# 17-FPGA-02b.net
KiCad netlist of a schematic drawn in Altium Designer
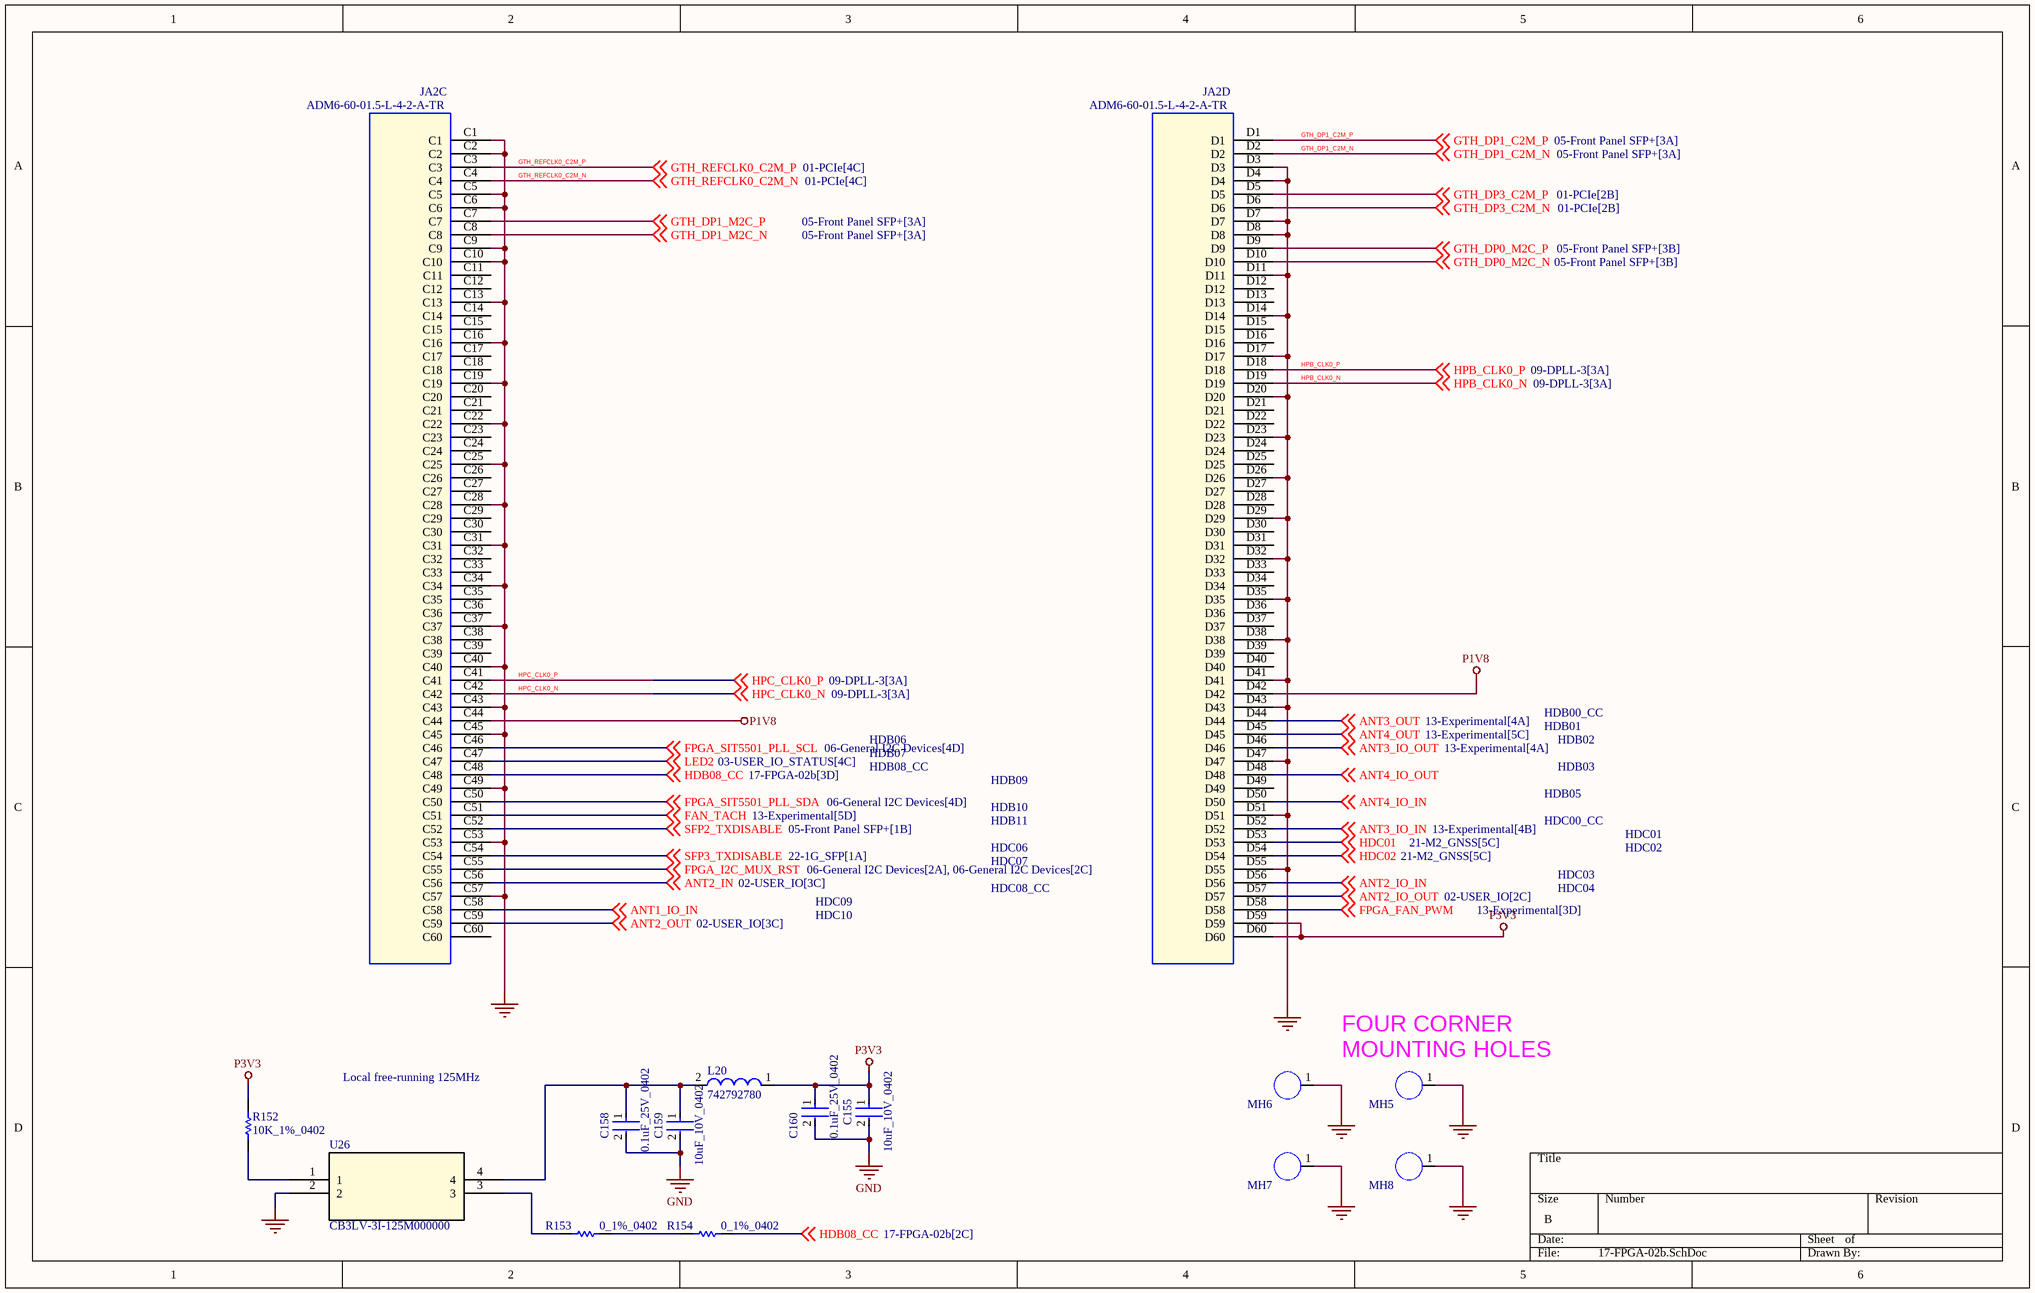
[diagram p0: 17-FPGA-02b.SchDoc]

(export (version "E")
  (design (tool "Eeschema 10.0.6"))
  (components
    (comp (ref "C155")
      (value "10uF_10V_0402")
      (footprint "FP-CL05A106MP5NUNC-MFG")
      (description "CAP CER 10UF 10V X5R 0402")
      (fields
        (field (name "OCTOPART") "https://octopart.com/cl05a106mp5nunc-samsung-22457395")
        (field (name "TOLERANCE") "20%")
      )
      (libsource (lib "Altium Content Vault") (part "b4654b650e69147ec39a6b967a45e02"))
    )
    (comp (ref "C158")
      (value "0.1uF_25V_0402")
      (footprint "FP-0402-L_1_0_1-W_0_5_0_1-IPC_C")
      (description "General Purpose Ceramic Capacitor, 0402, 100nF, 10%, X7R, 15%, 25V")
      (fields (field (name "VOLTAGE") "25V") (field (name "TOLERANCE") "10%"))
      (libsource (lib "Altium Content Vault") (part "b4654b650e69147ec39a6b967a45e02"))
    )
    (comp (ref "C159")
      (value "10uF_10V_0402")
      (footprint "FP-CL05A106MP5NUNC-MFG")
      (description "CAP CER 10UF 10V X5R 0402")
      (fields
        (field (name "OCTOPART") "https://octopart.com/cl05a106mp5nunc-samsung-22457395")
        (field (name "TOLERANCE") "20%")
      )
      (libsource (lib "Altium Content Vault") (part "b4654b650e69147ec39a6b967a45e02"))
    )
    (comp (ref "C160")
      (value "0.1uF_25V_0402")
      (footprint "FP-0402-L_1_0_1-W_0_5_0_1-IPC_C")
      (description "General Purpose Ceramic Capacitor, 0402, 100nF, 10%, X7R, 15%, 25V")
      (fields (field (name "VOLTAGE") "25V") (field (name "TOLERANCE") "10%"))
      (libsource (lib "Altium Content Vault") (part "b4654b650e69147ec39a6b967a45e02"))
    )
    (comp (ref "JA2")
      (value "ADM6-60-01.5-L-4-2-A-TR")
      (footprint "CON_SAMTEC_ADM6_60_4")
      (description "Conn Rcpt Male Vert 240 Pos 4x60 0.635mm P Black SMT")
      (fields (field (name "MANUFACTURER") "Samtec Inc.") (field (name "AGILE PART NUMBER") "CON-00383-01"))
      (libsource (lib "*") (part "SAMTEC-ADx6-60X4"))
    )
    (comp (ref "L20")
      (value "742792780")
      (footprint "SMD-0402")
      (description "SMD EMI Suppression Ferrite Bead WE-CBF, Z = 220 Ohm")
      (libsource (lib "Altium Content Vault") (part "PAS-IND-INDUCTOR-2"))
    )
    (comp (ref "MH5")
      (value "MH_NP_M3_SO_600")
      (footprint "MH_NP_M3_SO_600")
      (description "MOUNTING HOLE, NON-PLATED 3.4MM HOLE")
      (libsource (lib "*") (part "HOLE"))
    )
    (comp (ref "MH6")
      (value "MH_NP_M3_SO_600")
      (footprint "MH_NP_M3_SO_600")
      (description "MOUNTING HOLE, NON-PLATED 3.4MM HOLE")
      (libsource (lib "*") (part "HOLE"))
    )
    (comp (ref "MH7")
      (value "MH_NP_M3_SO_600")
      (footprint "MH_NP_M3_SO_600")
      (description "MOUNTING HOLE, NON-PLATED 3.4MM HOLE")
      (libsource (lib "*") (part "HOLE"))
    )
    (comp (ref "MH8")
      (value "MH_NP_M3_SO_600")
      (footprint "MH_NP_M3_SO_600")
      (description "MOUNTING HOLE, NON-PLATED 3.4MM HOLE")
      (libsource (lib "*") (part "HOLE"))
    )
    (comp (ref "R152")
      (value "10K_1%_0402")
      (footprint "RESC1005X40X25LL05T05")
      (description "Chip Resistor, 10 KOhm, +/- 1%, 0.1 W, -55 to 155 degC, 0402 (1005 Metric), RoHS, Tape and Reel")
      (fields (field (name "TOLERANCE") "1%") (field (name "MANUFACTURER") "Panasonic"))
      (libsource (lib "Altium Content Vault") (part "RES-2"))
    )
    (comp (ref "R153")
      (value "0_1%_0402")
      (footprint "RESC1005X40X25LL05T05")
      (description "Chip Resistor, 0 Ohm, 0.1 W, -55 to 155 degC, 0402 (1005 Metric), RoHS, Tape and Reel")
      (fields (field (name "MANUFACTURER") "Panasonic") (field (name "TOLERANCE") "5%"))
      (libsource (lib "Altium Content Vault") (part "RES-2"))
    )
    (comp (ref "R154")
      (value "0_1%_0402")
      (footprint "RESC1005X40X25LL05T05")
      (description "Chip Resistor, 0 Ohm, 0.1 W, -55 to 155 degC, 0402 (1005 Metric), RoHS, Tape and Reel")
      (fields (field (name "MANUFACTURER") "Panasonic") (field (name "TOLERANCE") "5%"))
      (libsource (lib "Altium Content Vault") (part "RES-2"))
    )
    (comp (ref "U26")
      (value "CB3LV-3I-125M000000")
      (footprint "CRYS_CB3LV-3I-14M7456_CTS")
      (description "No Description Available")
      (libsource (lib "CB3LV-3I-14M7456") (part "CB3LV-3I-14M7456"))
    )
  )
  (nets
    (net (code "1") (name "ANT1_IO_IN") (class "Default")
      (node (ref "JA2") (pin "C58") (pinfunction "C58_C58") (pintype "passive"))
    )
    (net (code "2") (name "ANT2_IN") (class "Default")
      (node (ref "JA2") (pin "C56") (pinfunction "C56_C56") (pintype "passive"))
    )
    (net (code "3") (name "ANT2_IO_IN") (class "Default")
      (node (ref "JA2") (pin "D56") (pinfunction "D56_D56") (pintype "passive"))
    )
    (net (code "4") (name "ANT2_IO_OUT") (class "Default")
      (node (ref "JA2") (pin "D57") (pinfunction "D57_D57") (pintype "passive"))
    )
    (net (code "5") (name "ANT2_OUT") (class "Default")
      (node (ref "JA2") (pin "C59") (pinfunction "C59_C59") (pintype "passive"))
    )
    (net (code "6") (name "ANT3_IO_IN") (class "Default")
      (node (ref "JA2") (pin "D52") (pinfunction "D52_D52") (pintype "passive"))
    )
    (net (code "7") (name "ANT3_IO_OUT") (class "Default")
      (node (ref "JA2") (pin "D46") (pinfunction "D46_D46") (pintype "passive"))
    )
    (net (code "8") (name "ANT3_OUT") (class "Default")
      (node (ref "JA2") (pin "D44") (pinfunction "D44_D44") (pintype "passive"))
    )
    (net (code "9") (name "ANT4_IO_IN") (class "Default")
      (node (ref "JA2") (pin "D50") (pinfunction "D50_D50") (pintype "passive"))
    )
    (net (code "10") (name "ANT4_IO_OUT") (class "Default")
      (node (ref "JA2") (pin "D48") (pinfunction "D48_D48") (pintype "passive"))
    )
    (net (code "11") (name "ANT4_OUT") (class "Default")
      (node (ref "JA2") (pin "D45") (pinfunction "D45_D45") (pintype "passive"))
    )
    (net (code "12") (name "FAN_TACH") (class "Default")
      (node (ref "JA2") (pin "C51") (pinfunction "C51_C51") (pintype "passive"))
    )
    (net (code "13") (name "FPGA_FAN_PWM") (class "Default")
      (node (ref "JA2") (pin "D58") (pinfunction "D58_D58") (pintype "passive"))
    )
    (net (code "14") (name "FPGA_I2C_MUX_RST") (class "Default")
      (node (ref "JA2") (pin "C55") (pinfunction "C55_C55") (pintype "passive"))
    )
    (net (code "15") (name "FPGA_SIT5501_PLL_SCL") (class "Default")
      (node (ref "JA2") (pin "C46") (pinfunction "C46_C46") (pintype "passive"))
    )
    (net (code "16") (name "FPGA_SIT5501_PLL_SDA") (class "Default")
      (node (ref "JA2") (pin "C50") (pinfunction "C50_C50") (pintype "passive"))
    )
    (net (code "17") (name "GND") (class "Default")
      (node (ref "C155") (pin "2") (pinfunction "2_2") (pintype "passive"))
      (node (ref "C158") (pin "2") (pinfunction "2_2") (pintype "passive"))
      (node (ref "C159") (pin "2") (pinfunction "2_2") (pintype "passive"))
      (node (ref "C160") (pin "2") (pinfunction "2_2") (pintype "passive"))
      (node (ref "JA2") (pin "C1") (pinfunction "C1_C1") (pintype "passive"))
      (node (ref "JA2") (pin "C10") (pinfunction "C10_C10") (pintype "passive"))
      (node (ref "JA2") (pin "C13") (pinfunction "C13_C13") (pintype "passive"))
      (node (ref "JA2") (pin "C16") (pinfunction "C16_C16") (pintype "passive"))
      (node (ref "JA2") (pin "C19") (pinfunction "C19_C19") (pintype "passive"))
      (node (ref "JA2") (pin "C2") (pinfunction "C2_C2") (pintype "passive"))
      (node (ref "JA2") (pin "C22") (pinfunction "C22_C22") (pintype "passive"))
      (node (ref "JA2") (pin "C25") (pinfunction "C25_C25") (pintype "passive"))
      (node (ref "JA2") (pin "C28") (pinfunction "C28_C28") (pintype "passive"))
      (node (ref "JA2") (pin "C31") (pinfunction "C31_C31") (pintype "passive"))
      (node (ref "JA2") (pin "C34") (pinfunction "C34_C34") (pintype "passive"))
      (node (ref "JA2") (pin "C37") (pinfunction "C37_C37") (pintype "passive"))
      (node (ref "JA2") (pin "C40") (pinfunction "C40_C40") (pintype "passive"))
      (node (ref "JA2") (pin "C43") (pinfunction "C43_C43") (pintype "passive"))
      (node (ref "JA2") (pin "C45") (pinfunction "C45_C45") (pintype "passive"))
      (node (ref "JA2") (pin "C49") (pinfunction "C49_C49") (pintype "passive"))
      (node (ref "JA2") (pin "C5") (pinfunction "C5_C5") (pintype "passive"))
      (node (ref "JA2") (pin "C53") (pinfunction "C53_C53") (pintype "passive"))
      (node (ref "JA2") (pin "C57") (pinfunction "C57_C57") (pintype "passive"))
      (node (ref "JA2") (pin "C6") (pinfunction "C6_C6") (pintype "passive"))
      (node (ref "JA2") (pin "C9") (pinfunction "C9_C9") (pintype "passive"))
      (node (ref "JA2") (pin "D11") (pinfunction "D11_D11") (pintype "passive"))
      (node (ref "JA2") (pin "D14") (pinfunction "D14_D14") (pintype "passive"))
      (node (ref "JA2") (pin "D17") (pinfunction "D17_D17") (pintype "passive"))
      (node (ref "JA2") (pin "D20") (pinfunction "D20_D20") (pintype "passive"))
      (node (ref "JA2") (pin "D23") (pinfunction "D23_D23") (pintype "passive"))
      (node (ref "JA2") (pin "D26") (pinfunction "D26_D26") (pintype "passive"))
      (node (ref "JA2") (pin "D29") (pinfunction "D29_D29") (pintype "passive"))
      (node (ref "JA2") (pin "D3") (pinfunction "D3_D3") (pintype "passive"))
      (node (ref "JA2") (pin "D32") (pinfunction "D32_D32") (pintype "passive"))
      (node (ref "JA2") (pin "D35") (pinfunction "D35_D35") (pintype "passive"))
      (node (ref "JA2") (pin "D38") (pinfunction "D38_D38") (pintype "passive"))
      (node (ref "JA2") (pin "D4") (pinfunction "D4_D4") (pintype "passive"))
      (node (ref "JA2") (pin "D41") (pinfunction "D41_D41") (pintype "passive"))
      (node (ref "JA2") (pin "D43") (pinfunction "D43_D43") (pintype "passive"))
      (node (ref "JA2") (pin "D47") (pinfunction "D47_D47") (pintype "passive"))
      (node (ref "JA2") (pin "D51") (pinfunction "D51_D51") (pintype "passive"))
      (node (ref "JA2") (pin "D55") (pinfunction "D55_D55") (pintype "passive"))
      (node (ref "JA2") (pin "D7") (pinfunction "D7_D7") (pintype "passive"))
      (node (ref "JA2") (pin "D8") (pinfunction "D8_D8") (pintype "passive"))
      (node (ref "MH5") (pin "1") (pinfunction "1_1") (pintype "passive"))
      (node (ref "MH6") (pin "1") (pinfunction "1_1") (pintype "passive"))
      (node (ref "MH7") (pin "1") (pinfunction "1_1") (pintype "passive"))
      (node (ref "MH8") (pin "1") (pinfunction "1_1") (pintype "passive"))
      (node (ref "U26") (pin "2") (pinfunction "2_2") (pintype "passive"))
    )
    (net (code "18") (name "GTH_DP0_M2C_N") (class "Default")
      (node (ref "JA2") (pin "D10") (pinfunction "D10_D10") (pintype "passive"))
    )
    (net (code "19") (name "GTH_DP0_M2C_P") (class "Default")
      (node (ref "JA2") (pin "D9") (pinfunction "D9_D9") (pintype "passive"))
    )
    (net (code "20") (name "GTH_DP1_C2M_N") (class "Default")
      (node (ref "JA2") (pin "D2") (pinfunction "D2_D2") (pintype "passive"))
    )
    (net (code "21") (name "GTH_DP1_C2M_P") (class "Default")
      (node (ref "JA2") (pin "D1") (pinfunction "D1_D1") (pintype "passive"))
    )
    (net (code "22") (name "GTH_DP1_M2C_N") (class "Default")
      (node (ref "JA2") (pin "C8") (pinfunction "C8_C8") (pintype "passive"))
    )
    (net (code "23") (name "GTH_DP1_M2C_P") (class "Default")
      (node (ref "JA2") (pin "C7") (pinfunction "C7_C7") (pintype "passive"))
    )
    (net (code "24") (name "GTH_DP3_C2M_N") (class "Default")
      (node (ref "JA2") (pin "D6") (pinfunction "D6_D6") (pintype "passive"))
    )
    (net (code "25") (name "GTH_DP3_C2M_P") (class "Default")
      (node (ref "JA2") (pin "D5") (pinfunction "D5_D5") (pintype "passive"))
    )
    (net (code "26") (name "GTH_REFCLK0_C2M_N") (class "Default")
      (node (ref "JA2") (pin "C4") (pinfunction "C4_C4") (pintype "passive"))
    )
    (net (code "27") (name "GTH_REFCLK0_C2M_P") (class "Default")
      (node (ref "JA2") (pin "C3") (pinfunction "C3_C3") (pintype "passive"))
    )
    (net (code "28") (name "HDB08_CC") (class "Default")
      (node (ref "JA2") (pin "C48") (pinfunction "C48_C48") (pintype "passive"))
      (node (ref "R154") (pin "2") (pinfunction "2_2") (pintype "passive"))
    )
    (net (code "29") (name "HDC01") (class "Default")
      (node (ref "JA2") (pin "D53") (pinfunction "D53_D53") (pintype "passive"))
    )
    (net (code "30") (name "HDC02") (class "Default")
      (node (ref "JA2") (pin "D54") (pinfunction "D54_D54") (pintype "passive"))
    )
    (net (code "31") (name "HPB_CLK0_N") (class "Default")
      (node (ref "JA2") (pin "D19") (pinfunction "D19_D19") (pintype "passive"))
    )
    (net (code "32") (name "HPB_CLK0_P") (class "Default")
      (node (ref "JA2") (pin "D18") (pinfunction "D18_D18") (pintype "passive"))
    )
    (net (code "33") (name "HPC_CLK0_N") (class "Default")
      (node (ref "JA2") (pin "C42") (pinfunction "C42_C42") (pintype "passive"))
    )
    (net (code "34") (name "HPC_CLK0_P") (class "Default")
      (node (ref "JA2") (pin "C41") (pinfunction "C41_C41") (pintype "passive"))
    )
    (net (code "35") (name "LED2") (class "Default")
      (node (ref "JA2") (pin "C47") (pinfunction "C47_C47") (pintype "passive"))
    )
    (net (code "36") (name "Net-(C158-Pad1)") (class "Default")
      (node (ref "C158") (pin "1") (pinfunction "1_1") (pintype "passive"))
      (node (ref "C159") (pin "1") (pinfunction "1_1") (pintype "passive"))
      (node (ref "L20") (pin "2") (pinfunction "2_2") (pintype "passive"))
      (node (ref "U26") (pin "4") (pinfunction "4_4") (pintype "passive"))
    )
    (net (code "37") (name "Net-(R152-Pad1)") (class "Default")
      (node (ref "R152") (pin "1") (pinfunction "1_1") (pintype "passive"))
      (node (ref "U26") (pin "1") (pinfunction "1_1") (pintype "passive"))
    )
    (net (code "38") (name "Net-(R153-Pad1)") (class "Default")
      (node (ref "R153") (pin "1") (pinfunction "1_1") (pintype "passive"))
      (node (ref "U26") (pin "3") (pinfunction "3_3") (pintype "passive"))
    )
    (net (code "39") (name "Net-(R153-Pad2)") (class "Default")
      (node (ref "R153") (pin "2") (pinfunction "2_2") (pintype "passive"))
      (node (ref "R154") (pin "1") (pinfunction "1_1") (pintype "passive"))
    )
    (net (code "40") (name "P1V8") (class "Default")
      (node (ref "JA2") (pin "C44") (pinfunction "C44_C44") (pintype "passive"))
      (node (ref "JA2") (pin "D42") (pinfunction "D42_D42") (pintype "passive"))
    )
    (net (code "41") (name "P3V3") (class "Default")
      (node (ref "C155") (pin "1") (pinfunction "1_1") (pintype "passive"))
      (node (ref "C160") (pin "1") (pinfunction "1_1") (pintype "passive"))
      (node (ref "JA2") (pin "D59") (pinfunction "D59_D59") (pintype "passive"))
      (node (ref "JA2") (pin "D60") (pinfunction "D60_D60") (pintype "passive"))
      (node (ref "L20") (pin "1") (pinfunction "1_1") (pintype "passive"))
      (node (ref "R152") (pin "2") (pinfunction "2_2") (pintype "passive"))
    )
    (net (code "42") (name "SFP2_TXDISABLE") (class "Default")
      (node (ref "JA2") (pin "C52") (pinfunction "C52_C52") (pintype "passive"))
    )
    (net (code "43") (name "SFP3_TXDISABLE") (class "Default")
      (node (ref "JA2") (pin "C54") (pinfunction "C54_C54") (pintype "passive"))
    )
    (net (code "44") (name "unconnected-(JA2-PadC11)") (class "Default")
      (node (ref "JA2") (pin "C11") (pinfunction "C11_C11") (pintype "passive"))
    )
    (net (code "45") (name "unconnected-(JA2-PadC12)") (class "Default")
      (node (ref "JA2") (pin "C12") (pinfunction "C12_C12") (pintype "passive"))
    )
    (net (code "46") (name "unconnected-(JA2-PadC14)") (class "Default")
      (node (ref "JA2") (pin "C14") (pinfunction "C14_C14") (pintype "passive"))
    )
    (net (code "47") (name "unconnected-(JA2-PadC15)") (class "Default")
      (node (ref "JA2") (pin "C15") (pinfunction "C15_C15") (pintype "passive"))
    )
    (net (code "48") (name "unconnected-(JA2-PadC17)") (class "Default")
      (node (ref "JA2") (pin "C17") (pinfunction "C17_C17") (pintype "passive"))
    )
    (net (code "49") (name "unconnected-(JA2-PadC18)") (class "Default")
      (node (ref "JA2") (pin "C18") (pinfunction "C18_C18") (pintype "passive"))
    )
    (net (code "50") (name "unconnected-(JA2-PadC20)") (class "Default")
      (node (ref "JA2") (pin "C20") (pinfunction "C20_C20") (pintype "passive"))
    )
    (net (code "51") (name "unconnected-(JA2-PadC21)") (class "Default")
      (node (ref "JA2") (pin "C21") (pinfunction "C21_C21") (pintype "passive"))
    )
    (net (code "52") (name "unconnected-(JA2-PadC23)") (class "Default")
      (node (ref "JA2") (pin "C23") (pinfunction "C23_C23") (pintype "passive"))
    )
    (net (code "53") (name "unconnected-(JA2-PadC24)") (class "Default")
      (node (ref "JA2") (pin "C24") (pinfunction "C24_C24") (pintype "passive"))
    )
    (net (code "54") (name "unconnected-(JA2-PadC26)") (class "Default")
      (node (ref "JA2") (pin "C26") (pinfunction "C26_C26") (pintype "passive"))
    )
    (net (code "55") (name "unconnected-(JA2-PadC27)") (class "Default")
      (node (ref "JA2") (pin "C27") (pinfunction "C27_C27") (pintype "passive"))
    )
    (net (code "56") (name "unconnected-(JA2-PadC29)") (class "Default")
      (node (ref "JA2") (pin "C29") (pinfunction "C29_C29") (pintype "passive"))
    )
    (net (code "57") (name "unconnected-(JA2-PadC30)") (class "Default")
      (node (ref "JA2") (pin "C30") (pinfunction "C30_C30") (pintype "passive"))
    )
    (net (code "58") (name "unconnected-(JA2-PadC32)") (class "Default")
      (node (ref "JA2") (pin "C32") (pinfunction "C32_C32") (pintype "passive"))
    )
    (net (code "59") (name "unconnected-(JA2-PadC33)") (class "Default")
      (node (ref "JA2") (pin "C33") (pinfunction "C33_C33") (pintype "passive"))
    )
    (net (code "60") (name "unconnected-(JA2-PadC35)") (class "Default")
      (node (ref "JA2") (pin "C35") (pinfunction "C35_C35") (pintype "passive"))
    )
    (net (code "61") (name "unconnected-(JA2-PadC36)") (class "Default")
      (node (ref "JA2") (pin "C36") (pinfunction "C36_C36") (pintype "passive"))
    )
    (net (code "62") (name "unconnected-(JA2-PadC38)") (class "Default")
      (node (ref "JA2") (pin "C38") (pinfunction "C38_C38") (pintype "passive"))
    )
    (net (code "63") (name "unconnected-(JA2-PadC39)") (class "Default")
      (node (ref "JA2") (pin "C39") (pinfunction "C39_C39") (pintype "passive"))
    )
    (net (code "64") (name "unconnected-(JA2-PadC60)") (class "Default")
      (node (ref "JA2") (pin "C60") (pinfunction "C60_C60") (pintype "passive"))
    )
    (net (code "65") (name "unconnected-(JA2-PadD12)") (class "Default")
      (node (ref "JA2") (pin "D12") (pinfunction "D12_D12") (pintype "passive"))
    )
    (net (code "66") (name "unconnected-(JA2-PadD13)") (class "Default")
      (node (ref "JA2") (pin "D13") (pinfunction "D13_D13") (pintype "passive"))
    )
    (net (code "67") (name "unconnected-(JA2-PadD15)") (class "Default")
      (node (ref "JA2") (pin "D15") (pinfunction "D15_D15") (pintype "passive"))
    )
    (net (code "68") (name "unconnected-(JA2-PadD16)") (class "Default")
      (node (ref "JA2") (pin "D16") (pinfunction "D16_D16") (pintype "passive"))
    )
    (net (code "69") (name "unconnected-(JA2-PadD21)") (class "Default")
      (node (ref "JA2") (pin "D21") (pinfunction "D21_D21") (pintype "passive"))
    )
    (net (code "70") (name "unconnected-(JA2-PadD22)") (class "Default")
      (node (ref "JA2") (pin "D22") (pinfunction "D22_D22") (pintype "passive"))
    )
    (net (code "71") (name "unconnected-(JA2-PadD24)") (class "Default")
      (node (ref "JA2") (pin "D24") (pinfunction "D24_D24") (pintype "passive"))
    )
    (net (code "72") (name "unconnected-(JA2-PadD25)") (class "Default")
      (node (ref "JA2") (pin "D25") (pinfunction "D25_D25") (pintype "passive"))
    )
    (net (code "73") (name "unconnected-(JA2-PadD27)") (class "Default")
      (node (ref "JA2") (pin "D27") (pinfunction "D27_D27") (pintype "passive"))
    )
    (net (code "74") (name "unconnected-(JA2-PadD28)") (class "Default")
      (node (ref "JA2") (pin "D28") (pinfunction "D28_D28") (pintype "passive"))
    )
    (net (code "75") (name "unconnected-(JA2-PadD30)") (class "Default")
      (node (ref "JA2") (pin "D30") (pinfunction "D30_D30") (pintype "passive"))
    )
    (net (code "76") (name "unconnected-(JA2-PadD31)") (class "Default")
      (node (ref "JA2") (pin "D31") (pinfunction "D31_D31") (pintype "passive"))
    )
    (net (code "77") (name "unconnected-(JA2-PadD33)") (class "Default")
      (node (ref "JA2") (pin "D33") (pinfunction "D33_D33") (pintype "passive"))
    )
    (net (code "78") (name "unconnected-(JA2-PadD34)") (class "Default")
      (node (ref "JA2") (pin "D34") (pinfunction "D34_D34") (pintype "passive"))
    )
    (net (code "79") (name "unconnected-(JA2-PadD36)") (class "Default")
      (node (ref "JA2") (pin "D36") (pinfunction "D36_D36") (pintype "passive"))
    )
    (net (code "80") (name "unconnected-(JA2-PadD37)") (class "Default")
      (node (ref "JA2") (pin "D37") (pinfunction "D37_D37") (pintype "passive"))
    )
    (net (code "81") (name "unconnected-(JA2-PadD39)") (class "Default")
      (node (ref "JA2") (pin "D39") (pinfunction "D39_D39") (pintype "passive"))
    )
    (net (code "82") (name "unconnected-(JA2-PadD40)") (class "Default")
      (node (ref "JA2") (pin "D40") (pinfunction "D40_D40") (pintype "passive"))
    )
    (net (code "83") (name "unconnected-(JA2-PadD49)") (class "Default")
      (node (ref "JA2") (pin "D49") (pinfunction "D49_D49") (pintype "passive"))
    )
  )
)
